# vca_A.net
KiCad netlist of a schematic drawn in Altium Designer
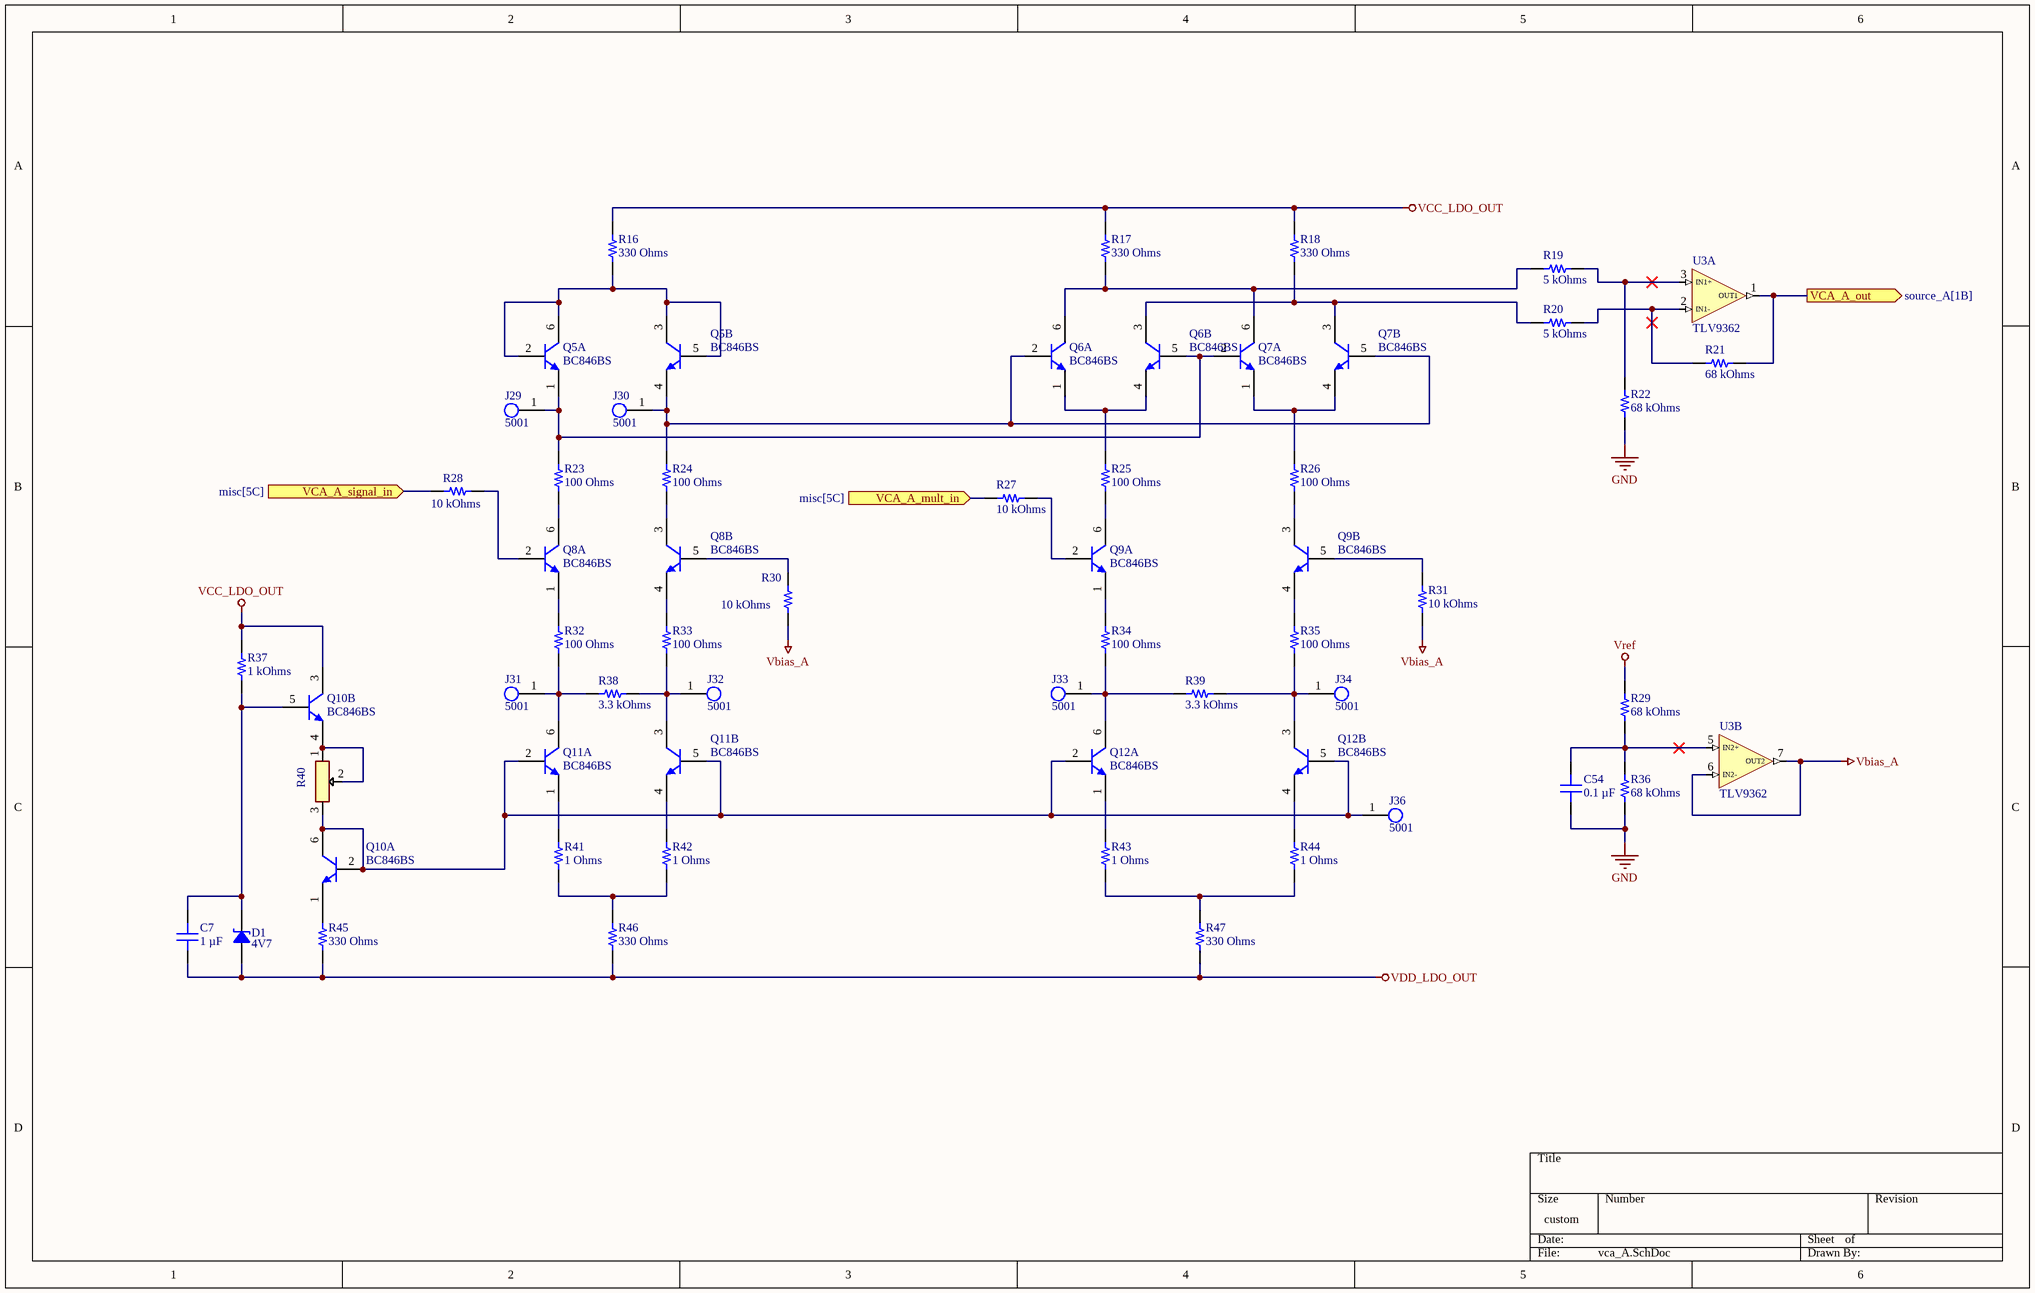
[diagram p0: vca_A.SchDoc]

(export (version "E")
  (design (tool "Eeschema 10.0.6"))
  (components
    (comp (ref "C7")
      (value "1 µF")
      (footprint "CAP 1206_3216 - 0.8MM")
      (description "CAP CER 1UF 50V X7R 1206")
      (fields
        (field (name "PART NUMBER") "885012208093")
        (field (name "CAPACITANCE") "1 µF")
        (field (name "MANUFACTURER") "Würth Elektronik")
      )
      (libsource (lib "Celestial Altium Library - altium_library") (part "Capacitor"))
    )
    (comp (ref "C54")
      (value "0.1 µF")
      (footprint "CAP 1206_3216 - 0.8MM")
      (description "CAP CER 0.1UF 50V X7R 1206")
      (fields
        (field (name "PART NUMBER") "885012208087")
        (field (name "CAPACITANCE") "0.1 µF")
        (field (name "MANUFACTURER") "Würth Elektronik")
      )
      (libsource (lib "Celestial Altium Library - altium_library") (part "Capacitor"))
    )
    (comp (ref "D1") (value "4V7") (footprint "SOD323") (libsource (lib "za_koncar") (part "BZX38450-C4V7X")))
    (comp (ref "J29")
      (value "5001")
      (footprint "FP-5001-MFG")
      (description "PC TEST POINT MINIATURE BLACK")
      (libsource (lib "za_koncar") (part "CMP-2000-05181-2"))
    )
    (comp (ref "J30")
      (value "5001")
      (footprint "FP-5001-MFG")
      (description "PC TEST POINT MINIATURE BLACK")
      (libsource (lib "za_koncar") (part "CMP-2000-05181-2"))
    )
    (comp (ref "J31")
      (value "5001")
      (footprint "FP-5001-MFG")
      (description "PC TEST POINT MINIATURE BLACK")
      (libsource (lib "za_koncar") (part "CMP-2000-05181-2"))
    )
    (comp (ref "J32")
      (value "5001")
      (footprint "FP-5001-MFG")
      (description "PC TEST POINT MINIATURE BLACK")
      (libsource (lib "za_koncar") (part "CMP-2000-05181-2"))
    )
    (comp (ref "J33")
      (value "5001")
      (footprint "FP-5001-MFG")
      (description "PC TEST POINT MINIATURE BLACK")
      (libsource (lib "za_koncar") (part "CMP-2000-05181-2"))
    )
    (comp (ref "J34")
      (value "5001")
      (footprint "FP-5001-MFG")
      (description "PC TEST POINT MINIATURE BLACK")
      (libsource (lib "za_koncar") (part "CMP-2000-05181-2"))
    )
    (comp (ref "J36")
      (value "5001")
      (footprint "FP-5001-MFG")
      (description "PC TEST POINT MINIATURE BLACK")
      (libsource (lib "za_koncar") (part "CMP-2000-05181-2"))
    )
    (comp (ref "Q5")
      (value "BC846BS")
      (footprint "TSOP65P210X110-6N")
      (description "65 V, 100 mA matched NPN/NPN general-purpose transistor")
      (libsource (lib "za_koncar") (part "BC846BS"))
    )
    (comp (ref "Q6")
      (value "BC846BS")
      (footprint "TSOP65P210X110-6N")
      (description "65 V, 100 mA matched NPN/NPN general-purpose transistor")
      (libsource (lib "za_koncar") (part "BC846BS"))
    )
    (comp (ref "Q7")
      (value "BC846BS")
      (footprint "TSOP65P210X110-6N")
      (description "65 V, 100 mA matched NPN/NPN general-purpose transistor")
      (libsource (lib "za_koncar") (part "BC846BS"))
    )
    (comp (ref "Q8")
      (value "BC846BS")
      (footprint "TSOP65P210X110-6N")
      (description "65 V, 100 mA matched NPN/NPN general-purpose transistor")
      (libsource (lib "za_koncar") (part "BC846BS"))
    )
    (comp (ref "Q9")
      (value "BC846BS")
      (footprint "TSOP65P210X110-6N")
      (description "65 V, 100 mA matched NPN/NPN general-purpose transistor")
      (libsource (lib "za_koncar") (part "BC846BS"))
    )
    (comp (ref "Q10")
      (value "BC846BS")
      (footprint "TSOP65P210X110-6N")
      (description "65 V, 100 mA matched NPN/NPN general-purpose transistor")
      (libsource (lib "za_koncar") (part "BC846BS"))
    )
    (comp (ref "Q11")
      (value "BC846BS")
      (footprint "TSOP65P210X110-6N")
      (description "65 V, 100 mA matched NPN/NPN general-purpose transistor")
      (libsource (lib "za_koncar") (part "BC846BS"))
    )
    (comp (ref "Q12")
      (value "BC846BS")
      (footprint "TSOP65P210X110-6N")
      (description "65 V, 100 mA matched NPN/NPN general-purpose transistor")
      (libsource (lib "za_koncar") (part "BC846BS"))
    )
    (comp (ref "R16")
      (value "330 Ohms")
      (footprint "YAGEO RES 1206_3216")
      (description "RES SMD 330 OHM 1% 1/4W 1206")
      (fields (field (name "PART NUMBER") "RT1206FRD07330RL") (field (name "MANUFACTURER") "Yageo"))
      (libsource (lib "Celestial Altium Library - altium_library") (part "Resistor"))
    )
    (comp (ref "R17")
      (value "330 Ohms")
      (footprint "YAGEO RES 1206_3216")
      (description "RES SMD 330 OHM 1% 1/4W 1206")
      (fields (field (name "PART NUMBER") "RT1206FRD07330RL") (field (name "MANUFACTURER") "Yageo"))
      (libsource (lib "Celestial Altium Library - altium_library") (part "Resistor"))
    )
    (comp (ref "R18")
      (value "330 Ohms")
      (footprint "YAGEO RES 1206_3216")
      (description "RES SMD 330 OHM 1% 1/4W 1206")
      (fields (field (name "PART NUMBER") "RT1206FRD07330RL") (field (name "MANUFACTURER") "Yageo"))
      (libsource (lib "Celestial Altium Library - altium_library") (part "Resistor"))
    )
    (comp (ref "R19")
      (value "5 kOhms")
      (footprint "YAGEO RES 1206_3216")
      (description "RES 5K OHM 1% 1/4W 1206")
      (fields (field (name "PART NUMBER") "RT1206FRE075KL") (field (name "MANUFACTURER") "Yageo"))
      (libsource (lib "Celestial Altium Library - altium_library") (part "Resistor"))
    )
    (comp (ref "R20")
      (value "5 kOhms")
      (footprint "YAGEO RES 1206_3216")
      (description "RES 5K OHM 1% 1/4W 1206")
      (fields (field (name "PART NUMBER") "RT1206FRE075KL") (field (name "MANUFACTURER") "Yageo"))
      (libsource (lib "Celestial Altium Library - altium_library") (part "Resistor"))
    )
    (comp (ref "R21")
      (value "68 kOhms")
      (footprint "YAGEO RES 1206_3216")
      (description "RES SMD 68K OHM 1% 1/4W 1206")
      (fields (field (name "PART NUMBER") "RT1206FRE0768KL") (field (name "MANUFACTURER") "Yageo"))
      (libsource (lib "Celestial Altium Library - altium_library") (part "Resistor"))
    )
    (comp (ref "R22")
      (value "68 kOhms")
      (footprint "YAGEO RES 1206_3216")
      (description "RES SMD 68K OHM 1% 1/4W 1206")
      (fields (field (name "PART NUMBER") "RT1206FRE0768KL") (field (name "MANUFACTURER") "Yageo"))
      (libsource (lib "Celestial Altium Library - altium_library") (part "Resistor"))
    )
    (comp (ref "R23")
      (value "100 Ohms")
      (footprint "YAGEO RES 1206_3216")
      (description "RES SMD 100 OHM 1% 1/4W 1206")
      (fields (field (name "PART NUMBER") "RT1206FRD07100RL") (field (name "MANUFACTURER") "Yageo"))
      (libsource (lib "Celestial Altium Library - altium_library") (part "Resistor"))
    )
    (comp (ref "R24")
      (value "100 Ohms")
      (footprint "YAGEO RES 1206_3216")
      (description "RES SMD 100 OHM 1% 1/4W 1206")
      (fields (field (name "PART NUMBER") "RT1206FRD07100RL") (field (name "MANUFACTURER") "Yageo"))
      (libsource (lib "Celestial Altium Library - altium_library") (part "Resistor"))
    )
    (comp (ref "R25")
      (value "100 Ohms")
      (footprint "YAGEO RES 1206_3216")
      (description "RES SMD 100 OHM 1% 1/4W 1206")
      (fields (field (name "PART NUMBER") "RT1206FRD07100RL") (field (name "MANUFACTURER") "Yageo"))
      (libsource (lib "Celestial Altium Library - altium_library") (part "Resistor"))
    )
    (comp (ref "R26")
      (value "100 Ohms")
      (footprint "YAGEO RES 1206_3216")
      (description "RES SMD 100 OHM 1% 1/4W 1206")
      (fields (field (name "PART NUMBER") "RT1206FRD07100RL") (field (name "MANUFACTURER") "Yageo"))
      (libsource (lib "Celestial Altium Library - altium_library") (part "Resistor"))
    )
    (comp (ref "R27")
      (value "10 kOhms")
      (footprint "YAGEO RES 1206_3216")
      (description "RES SMD 10K OHM 1% 1/4W 1206")
      (fields (field (name "PART NUMBER") "RT1206FRE0710KL") (field (name "MANUFACTURER") "Yageo"))
      (libsource (lib "Celestial Altium Library - altium_library") (part "Resistor"))
    )
    (comp (ref "R28")
      (value "10 kOhms")
      (footprint "YAGEO RES 1206_3216")
      (description "RES SMD 10K OHM 1% 1/4W 1206")
      (fields (field (name "PART NUMBER") "RT1206FRE0710KL") (field (name "MANUFACTURER") "Yageo"))
      (libsource (lib "Celestial Altium Library - altium_library") (part "Resistor"))
    )
    (comp (ref "R29")
      (value "68 kOhms")
      (footprint "YAGEO RES 1206_3216")
      (description "RES SMD 68K OHM 1% 1/4W 1206")
      (fields (field (name "PART NUMBER") "RT1206FRE0768KL") (field (name "MANUFACTURER") "Yageo"))
      (libsource (lib "Celestial Altium Library - altium_library") (part "Resistor"))
    )
    (comp (ref "R30")
      (value "10 kOhms")
      (footprint "YAGEO RES 1206_3216")
      (description "RES SMD 10K OHM 1% 1/4W 1206")
      (fields (field (name "PART NUMBER") "RT1206FRE0710KL") (field (name "MANUFACTURER") "Yageo"))
      (libsource (lib "Celestial Altium Library - altium_library") (part "Resistor"))
    )
    (comp (ref "R31")
      (value "10 kOhms")
      (footprint "YAGEO RES 1206_3216")
      (description "RES SMD 10K OHM 1% 1/4W 1206")
      (fields (field (name "PART NUMBER") "RT1206FRE0710KL") (field (name "MANUFACTURER") "Yageo"))
      (libsource (lib "Celestial Altium Library - altium_library") (part "Resistor"))
    )
    (comp (ref "R32")
      (value "100 Ohms")
      (footprint "YAGEO RES 1206_3216")
      (description "RES SMD 100 OHM 1% 1/4W 1206")
      (fields (field (name "PART NUMBER") "RT1206FRD07100RL") (field (name "MANUFACTURER") "Yageo"))
      (libsource (lib "Celestial Altium Library - altium_library") (part "Resistor"))
    )
    (comp (ref "R33")
      (value "100 Ohms")
      (footprint "YAGEO RES 1206_3216")
      (description "RES SMD 100 OHM 1% 1/4W 1206")
      (fields (field (name "PART NUMBER") "RT1206FRD07100RL") (field (name "MANUFACTURER") "Yageo"))
      (libsource (lib "Celestial Altium Library - altium_library") (part "Resistor"))
    )
    (comp (ref "R34")
      (value "100 Ohms")
      (footprint "YAGEO RES 1206_3216")
      (description "RES SMD 100 OHM 1% 1/4W 1206")
      (fields (field (name "PART NUMBER") "RT1206FRD07100RL") (field (name "MANUFACTURER") "Yageo"))
      (libsource (lib "Celestial Altium Library - altium_library") (part "Resistor"))
    )
    (comp (ref "R35")
      (value "100 Ohms")
      (footprint "YAGEO RES 1206_3216")
      (description "RES SMD 100 OHM 1% 1/4W 1206")
      (fields (field (name "PART NUMBER") "RT1206FRD07100RL") (field (name "MANUFACTURER") "Yageo"))
      (libsource (lib "Celestial Altium Library - altium_library") (part "Resistor"))
    )
    (comp (ref "R36")
      (value "68 kOhms")
      (footprint "YAGEO RES 1206_3216")
      (description "RES SMD 68K OHM 1% 1/4W 1206")
      (fields (field (name "PART NUMBER") "RT1206FRE0768KL") (field (name "MANUFACTURER") "Yageo"))
      (libsource (lib "Celestial Altium Library - altium_library") (part "Resistor"))
    )
    (comp (ref "R37")
      (value "1 kOhms")
      (footprint "YAGEO RES 1206_3216")
      (description "RES SMD 1K OHM 1% 1/4W 1206")
      (fields (field (name "PART NUMBER") "RT1206FRE071KL") (field (name "MANUFACTURER") "Yageo"))
      (libsource (lib "Celestial Altium Library - altium_library") (part "Resistor"))
    )
    (comp (ref "R38")
      (value "3.3 kOhms")
      (footprint "YAGEO RES 1206_3216")
      (description "RES SMD 3.3K OHM 1% 1/4W 1206")
      (fields (field (name "PART NUMBER") "RT1206FRE073K3L") (field (name "MANUFACTURER") "Yageo"))
      (libsource (lib "Celestial Altium Library - altium_library") (part "Resistor"))
    )
    (comp (ref "R39")
      (value "3.3 kOhms")
      (footprint "YAGEO RES 1206_3216")
      (description "RES SMD 3.3K OHM 1% 1/4W 1206")
      (fields (field (name "PART NUMBER") "RT1206FRE073K3L") (field (name "MANUFACTURER") "Yageo"))
      (libsource (lib "Celestial Altium Library - altium_library") (part "Resistor"))
    )
    (comp (ref "R40")
      (value "TC33X-2-502G")
      (footprint "TC33X2503E")
      (description "Resistor")
      (fields (field (name "MOUSER PART NUMBER") "652-TC33X-2-502G"))
      (libsource (lib "za_koncar") (part "TC33X-2-502G"))
    )
    (comp (ref "R41")
      (value "1 Ohms")
      (footprint "YAGEO RES 1206_3216")
      (description "RES 1 OHM 0.1% 1/4W 1206")
      (fields (field (name "PART NUMBER") "RT1206BRD071RL") (field (name "MANUFACTURER") "Yageo"))
      (libsource (lib "Celestial Altium Library - altium_library") (part "Resistor"))
    )
    (comp (ref "R42")
      (value "1 Ohms")
      (footprint "YAGEO RES 1206_3216")
      (description "RES 1 OHM 0.1% 1/4W 1206")
      (fields (field (name "PART NUMBER") "RT1206BRD071RL") (field (name "MANUFACTURER") "Yageo"))
      (libsource (lib "Celestial Altium Library - altium_library") (part "Resistor"))
    )
    (comp (ref "R43")
      (value "1 Ohms")
      (footprint "YAGEO RES 1206_3216")
      (description "RES 1 OHM 0.1% 1/4W 1206")
      (fields (field (name "PART NUMBER") "RT1206BRD071RL") (field (name "MANUFACTURER") "Yageo"))
      (libsource (lib "Celestial Altium Library - altium_library") (part "Resistor"))
    )
    (comp (ref "R44")
      (value "1 Ohms")
      (footprint "YAGEO RES 1206_3216")
      (description "RES 1 OHM 0.1% 1/4W 1206")
      (fields (field (name "PART NUMBER") "RT1206BRD071RL") (field (name "MANUFACTURER") "Yageo"))
      (libsource (lib "Celestial Altium Library - altium_library") (part "Resistor"))
    )
    (comp (ref "R45")
      (value "330 Ohms")
      (footprint "YAGEO RES 1206_3216")
      (description "RES SMD 330 OHM 1% 1/4W 1206")
      (fields (field (name "PART NUMBER") "RT1206FRD07330RL") (field (name "MANUFACTURER") "Yageo"))
      (libsource (lib "Celestial Altium Library - altium_library") (part "Resistor"))
    )
    (comp (ref "R46")
      (value "330 Ohms")
      (footprint "YAGEO RES 1206_3216")
      (description "RES SMD 330 OHM 1% 1/4W 1206")
      (fields (field (name "PART NUMBER") "RT1206FRD07330RL") (field (name "MANUFACTURER") "Yageo"))
      (libsource (lib "Celestial Altium Library - altium_library") (part "Resistor"))
    )
    (comp (ref "R47")
      (value "330 Ohms")
      (footprint "YAGEO RES 1206_3216")
      (description "RES SMD 330 OHM 1% 1/4W 1206")
      (fields (field (name "PART NUMBER") "RT1206FRD07330RL") (field (name "MANUFACTURER") "Yageo"))
      (libsource (lib "Celestial Altium Library - altium_library") (part "Resistor"))
    )
    (comp (ref "U3")
      (value "TLV9362")
      (footprint "za_koncar:SOIC8-127P600X175-8N")
      (description "TLV936x 10-MHz, 40-V, RRO, Operational Amplifie")
      (libsource (lib "za_koncar") (part "TLV9362"))
    )
  )
  (nets
    (net (code "1") (name "/VCA_A_mult_in") (class "Default")
      (node (ref "R27") (pin "1") (pinfunction "1_1") (pintype "passive"))
    )
    (net (code "2") (name "/VCA_A_out") (class "Default")
      (node (ref "R21") (pin "1") (pinfunction "1_1") (pintype "passive"))
      (node (ref "U3") (pin "1") (pinfunction "OUT1_1") (pintype "output"))
    )
    (net (code "3") (name "/VCA_A_signal_in") (class "Default")
      (node (ref "R28") (pin "1") (pinfunction "1_1") (pintype "passive"))
    )
    (net (code "4") (name "GND") (class "Default")
      (node (ref "C54") (pin "1") (pinfunction "1_1") (pintype "passive"))
      (node (ref "R22") (pin "2") (pinfunction "2_2") (pintype "passive"))
      (node (ref "R36") (pin "1") (pinfunction "1_1") (pintype "passive"))
    )
    (net (code "5") (name "Net-(Q5A-B1)") (class "Default")
      (node (ref "Q5") (pin "2") (pinfunction "B1_2") (pintype "passive"))
      (node (ref "Q5") (pin "3") (pinfunction "C2_3") (pintype "passive"))
      (node (ref "Q5") (pin "5") (pinfunction "B2_5") (pintype "passive"))
      (node (ref "Q5") (pin "6") (pinfunction "C1_6") (pintype "passive"))
      (node (ref "R16") (pin "1") (pinfunction "1_1") (pintype "passive"))
    )
    (net (code "6") (name "Net-(Q5A-E1)") (class "Default")
      (node (ref "J29") (pin "1") (pinfunction "1_1") (pintype "passive"))
      (node (ref "Q5") (pin "1") (pinfunction "E1_1") (pintype "passive"))
      (node (ref "Q6") (pin "5") (pinfunction "B2_5") (pintype "passive"))
      (node (ref "Q7") (pin "2") (pinfunction "B1_2") (pintype "passive"))
      (node (ref "R23") (pin "2") (pinfunction "2_2") (pintype "passive"))
    )
    (net (code "7") (name "Net-(Q5B-E2)") (class "Default")
      (node (ref "J30") (pin "1") (pinfunction "1_1") (pintype "passive"))
      (node (ref "Q5") (pin "4") (pinfunction "E2_4") (pintype "passive"))
      (node (ref "Q6") (pin "2") (pinfunction "B1_2") (pintype "passive"))
      (node (ref "Q7") (pin "5") (pinfunction "B2_5") (pintype "passive"))
      (node (ref "R24") (pin "2") (pinfunction "2_2") (pintype "passive"))
    )
    (net (code "8") (name "Net-(Q6A-C1)") (class "Default")
      (node (ref "Q6") (pin "6") (pinfunction "C1_6") (pintype "passive"))
      (node (ref "Q7") (pin "6") (pinfunction "C1_6") (pintype "passive"))
      (node (ref "R17") (pin "1") (pinfunction "1_1") (pintype "passive"))
      (node (ref "R19") (pin "2") (pinfunction "2_2") (pintype "passive"))
    )
    (net (code "9") (name "Net-(Q6A-E1)") (class "Default")
      (node (ref "Q6") (pin "1") (pinfunction "E1_1") (pintype "passive"))
      (node (ref "Q6") (pin "4") (pinfunction "E2_4") (pintype "passive"))
      (node (ref "R25") (pin "2") (pinfunction "2_2") (pintype "passive"))
    )
    (net (code "10") (name "Net-(Q6B-C2)") (class "Default")
      (node (ref "Q6") (pin "3") (pinfunction "C2_3") (pintype "passive"))
      (node (ref "Q7") (pin "3") (pinfunction "C2_3") (pintype "passive"))
      (node (ref "R18") (pin "1") (pinfunction "1_1") (pintype "passive"))
      (node (ref "R20") (pin "2") (pinfunction "2_2") (pintype "passive"))
    )
    (net (code "11") (name "Net-(Q7A-E1)") (class "Default")
      (node (ref "Q7") (pin "1") (pinfunction "E1_1") (pintype "passive"))
      (node (ref "Q7") (pin "4") (pinfunction "E2_4") (pintype "passive"))
      (node (ref "R26") (pin "2") (pinfunction "2_2") (pintype "passive"))
    )
    (net (code "12") (name "Net-(Q8A-B1)") (class "Default")
      (node (ref "Q8") (pin "2") (pinfunction "B1_2") (pintype "passive"))
      (node (ref "R28") (pin "2") (pinfunction "2_2") (pintype "passive"))
    )
    (net (code "13") (name "Net-(Q8A-C1)") (class "Default")
      (node (ref "Q8") (pin "6") (pinfunction "C1_6") (pintype "passive"))
      (node (ref "R23") (pin "1") (pinfunction "1_1") (pintype "passive"))
    )
    (net (code "14") (name "Net-(Q8A-E1)") (class "Default")
      (node (ref "Q8") (pin "1") (pinfunction "E1_1") (pintype "passive"))
      (node (ref "R32") (pin "2") (pinfunction "2_2") (pintype "passive"))
    )
    (net (code "15") (name "Net-(Q8B-B2)") (class "Default")
      (node (ref "Q8") (pin "5") (pinfunction "B2_5") (pintype "passive"))
      (node (ref "R30") (pin "2") (pinfunction "2_2") (pintype "passive"))
    )
    (net (code "16") (name "Net-(Q8B-C2)") (class "Default")
      (node (ref "Q8") (pin "3") (pinfunction "C2_3") (pintype "passive"))
      (node (ref "R24") (pin "1") (pinfunction "1_1") (pintype "passive"))
    )
    (net (code "17") (name "Net-(Q8B-E2)") (class "Default")
      (node (ref "Q8") (pin "4") (pinfunction "E2_4") (pintype "passive"))
      (node (ref "R33") (pin "2") (pinfunction "2_2") (pintype "passive"))
    )
    (net (code "18") (name "Net-(Q9A-B1)") (class "Default")
      (node (ref "Q9") (pin "2") (pinfunction "B1_2") (pintype "passive"))
      (node (ref "R27") (pin "2") (pinfunction "2_2") (pintype "passive"))
    )
    (net (code "19") (name "Net-(Q9A-C1)") (class "Default")
      (node (ref "Q9") (pin "6") (pinfunction "C1_6") (pintype "passive"))
      (node (ref "R25") (pin "1") (pinfunction "1_1") (pintype "passive"))
    )
    (net (code "20") (name "Net-(Q9A-E1)") (class "Default")
      (node (ref "Q9") (pin "1") (pinfunction "E1_1") (pintype "passive"))
      (node (ref "R34") (pin "2") (pinfunction "2_2") (pintype "passive"))
    )
    (net (code "21") (name "Net-(Q9B-B2)") (class "Default")
      (node (ref "Q9") (pin "5") (pinfunction "B2_5") (pintype "passive"))
      (node (ref "R31") (pin "2") (pinfunction "2_2") (pintype "passive"))
    )
    (net (code "22") (name "Net-(Q9B-C2)") (class "Default")
      (node (ref "Q9") (pin "3") (pinfunction "C2_3") (pintype "passive"))
      (node (ref "R26") (pin "1") (pinfunction "1_1") (pintype "passive"))
    )
    (net (code "23") (name "Net-(Q9B-E2)") (class "Default")
      (node (ref "Q9") (pin "4") (pinfunction "E2_4") (pintype "passive"))
      (node (ref "R35") (pin "2") (pinfunction "2_2") (pintype "passive"))
    )
    (net (code "24") (name "Net-(Q10A-B1)") (class "Default")
      (node (ref "J36") (pin "1") (pinfunction "1_1") (pintype "passive"))
      (node (ref "Q10") (pin "2") (pinfunction "B1_2") (pintype "passive"))
      (node (ref "Q10") (pin "6") (pinfunction "C1_6") (pintype "passive"))
      (node (ref "Q11") (pin "2") (pinfunction "B1_2") (pintype "passive"))
      (node (ref "Q11") (pin "5") (pinfunction "B2_5") (pintype "passive"))
      (node (ref "Q12") (pin "2") (pinfunction "B1_2") (pintype "passive"))
      (node (ref "Q12") (pin "5") (pinfunction "B2_5") (pintype "passive"))
      (node (ref "R40") (pin "3") (pinfunction "CW_3") (pintype "passive"))
    )
    (net (code "25") (name "Net-(Q10A-E1)") (class "Default")
      (node (ref "Q10") (pin "1") (pinfunction "E1_1") (pintype "passive"))
      (node (ref "R45") (pin "2") (pinfunction "2_2") (pintype "passive"))
    )
    (net (code "26") (name "Net-(Q10B-B2)") (class "Default")
      (node (ref "C7") (pin "2") (pinfunction "2_2") (pintype "passive"))
      (node (ref "D1") (pin "2") (pinfunction "2_2") (pintype "passive"))
      (node (ref "Q10") (pin "5") (pinfunction "B2_5") (pintype "passive"))
      (node (ref "R37") (pin "1") (pinfunction "1_1") (pintype "passive"))
    )
    (net (code "27") (name "Net-(Q10B-E2)") (class "Default")
      (node (ref "Q10") (pin "4") (pinfunction "E2_4") (pintype "passive"))
      (node (ref "R40") (pin "1") (pinfunction "CCW_1") (pintype "passive"))
      (node (ref "R40") (pin "2") (pinfunction "W_2") (pintype "passive"))
    )
    (net (code "28") (name "Net-(Q11A-C1)") (class "Default")
      (node (ref "J31") (pin "1") (pinfunction "1_1") (pintype "passive"))
      (node (ref "Q11") (pin "6") (pinfunction "C1_6") (pintype "passive"))
      (node (ref "R32") (pin "1") (pinfunction "1_1") (pintype "passive"))
      (node (ref "R38") (pin "2") (pinfunction "2_2") (pintype "passive"))
    )
    (net (code "29") (name "Net-(Q11A-E1)") (class "Default")
      (node (ref "Q11") (pin "1") (pinfunction "E1_1") (pintype "passive"))
      (node (ref "R41") (pin "2") (pinfunction "2_2") (pintype "passive"))
    )
    (net (code "30") (name "Net-(Q11B-C2)") (class "Default")
      (node (ref "J32") (pin "1") (pinfunction "1_1") (pintype "passive"))
      (node (ref "Q11") (pin "3") (pinfunction "C2_3") (pintype "passive"))
      (node (ref "R33") (pin "1") (pinfunction "1_1") (pintype "passive"))
      (node (ref "R38") (pin "1") (pinfunction "1_1") (pintype "passive"))
    )
    (net (code "31") (name "Net-(Q11B-E2)") (class "Default")
      (node (ref "Q11") (pin "4") (pinfunction "E2_4") (pintype "passive"))
      (node (ref "R42") (pin "2") (pinfunction "2_2") (pintype "passive"))
    )
    (net (code "32") (name "Net-(Q12A-C1)") (class "Default")
      (node (ref "J33") (pin "1") (pinfunction "1_1") (pintype "passive"))
      (node (ref "Q12") (pin "6") (pinfunction "C1_6") (pintype "passive"))
      (node (ref "R34") (pin "1") (pinfunction "1_1") (pintype "passive"))
      (node (ref "R39") (pin "2") (pinfunction "2_2") (pintype "passive"))
    )
    (net (code "33") (name "Net-(Q12A-E1)") (class "Default")
      (node (ref "Q12") (pin "1") (pinfunction "E1_1") (pintype "passive"))
      (node (ref "R43") (pin "2") (pinfunction "2_2") (pintype "passive"))
    )
    (net (code "34") (name "Net-(Q12B-C2)") (class "Default")
      (node (ref "J34") (pin "1") (pinfunction "1_1") (pintype "passive"))
      (node (ref "Q12") (pin "3") (pinfunction "C2_3") (pintype "passive"))
      (node (ref "R35") (pin "1") (pinfunction "1_1") (pintype "passive"))
      (node (ref "R39") (pin "1") (pinfunction "1_1") (pintype "passive"))
    )
    (net (code "35") (name "Net-(Q12B-E2)") (class "Default")
      (node (ref "Q12") (pin "4") (pinfunction "E2_4") (pintype "passive"))
      (node (ref "R44") (pin "2") (pinfunction "2_2") (pintype "passive"))
    )
    (net (code "36") (name "Net-(R41-Pad1)") (class "Default")
      (node (ref "R41") (pin "1") (pinfunction "1_1") (pintype "passive"))
      (node (ref "R42") (pin "1") (pinfunction "1_1") (pintype "passive"))
      (node (ref "R46") (pin "2") (pinfunction "2_2") (pintype "passive"))
    )
    (net (code "37") (name "Net-(R43-Pad1)") (class "Default")
      (node (ref "R43") (pin "1") (pinfunction "1_1") (pintype "passive"))
      (node (ref "R44") (pin "1") (pinfunction "1_1") (pintype "passive"))
      (node (ref "R47") (pin "2") (pinfunction "2_2") (pintype "passive"))
    )
    (net (code "38") (name "Net-(U3A-IN1+)") (class "Default")
      (node (ref "R19") (pin "1") (pinfunction "1_1") (pintype "passive"))
      (node (ref "R22") (pin "1") (pinfunction "1_1") (pintype "passive"))
      (node (ref "U3") (pin "3") (pinfunction "IN1+_3") (pintype "input"))
    )
    (net (code "39") (name "Net-(U3A-IN1-)") (class "Default")
      (node (ref "R20") (pin "1") (pinfunction "1_1") (pintype "passive"))
      (node (ref "R21") (pin "2") (pinfunction "2_2") (pintype "passive"))
      (node (ref "U3") (pin "2") (pinfunction "IN1-_2") (pintype "input"))
    )
    (net (code "40") (name "Net-(U3B-IN2+)") (class "Default")
      (node (ref "C54") (pin "2") (pinfunction "2_2") (pintype "passive"))
      (node (ref "R29") (pin "1") (pinfunction "1_1") (pintype "passive"))
      (node (ref "R36") (pin "2") (pinfunction "2_2") (pintype "passive"))
      (node (ref "U3") (pin "5") (pinfunction "IN2+_5") (pintype "input"))
    )
    (net (code "41") (name "VCC_LDO_OUT") (class "Default")
      (node (ref "Q10") (pin "3") (pinfunction "C2_3") (pintype "passive"))
      (node (ref "R16") (pin "2") (pinfunction "2_2") (pintype "passive"))
      (node (ref "R17") (pin "2") (pinfunction "2_2") (pintype "passive"))
      (node (ref "R18") (pin "2") (pinfunction "2_2") (pintype "passive"))
      (node (ref "R37") (pin "2") (pinfunction "2_2") (pintype "passive"))
    )
    (net (code "42") (name "VDD_LDO_OUT") (class "Default")
      (node (ref "C7") (pin "1") (pinfunction "1_1") (pintype "passive"))
      (node (ref "D1") (pin "1") (pinfunction "1_1") (pintype "passive"))
      (node (ref "R45") (pin "1") (pinfunction "1_1") (pintype "passive"))
      (node (ref "R46") (pin "1") (pinfunction "1_1") (pintype "passive"))
      (node (ref "R47") (pin "1") (pinfunction "1_1") (pintype "passive"))
    )
    (net (code "43") (name "Vbias_A") (class "Default")
      (node (ref "R30") (pin "1") (pinfunction "1_1") (pintype "passive"))
      (node (ref "R31") (pin "1") (pinfunction "1_1") (pintype "passive"))
      (node (ref "U3") (pin "6") (pinfunction "IN2-_6") (pintype "input"))
      (node (ref "U3") (pin "7") (pinfunction "OUT2_7") (pintype "output"))
    )
    (net (code "44") (name "Vref") (class "Default")
      (node (ref "R29") (pin "2") (pinfunction "2_2") (pintype "passive"))
    )
  )
)
